# avoccado-avr-pcb-yolandi.net
KiCad netlist of a schematic drawn in EAGLE
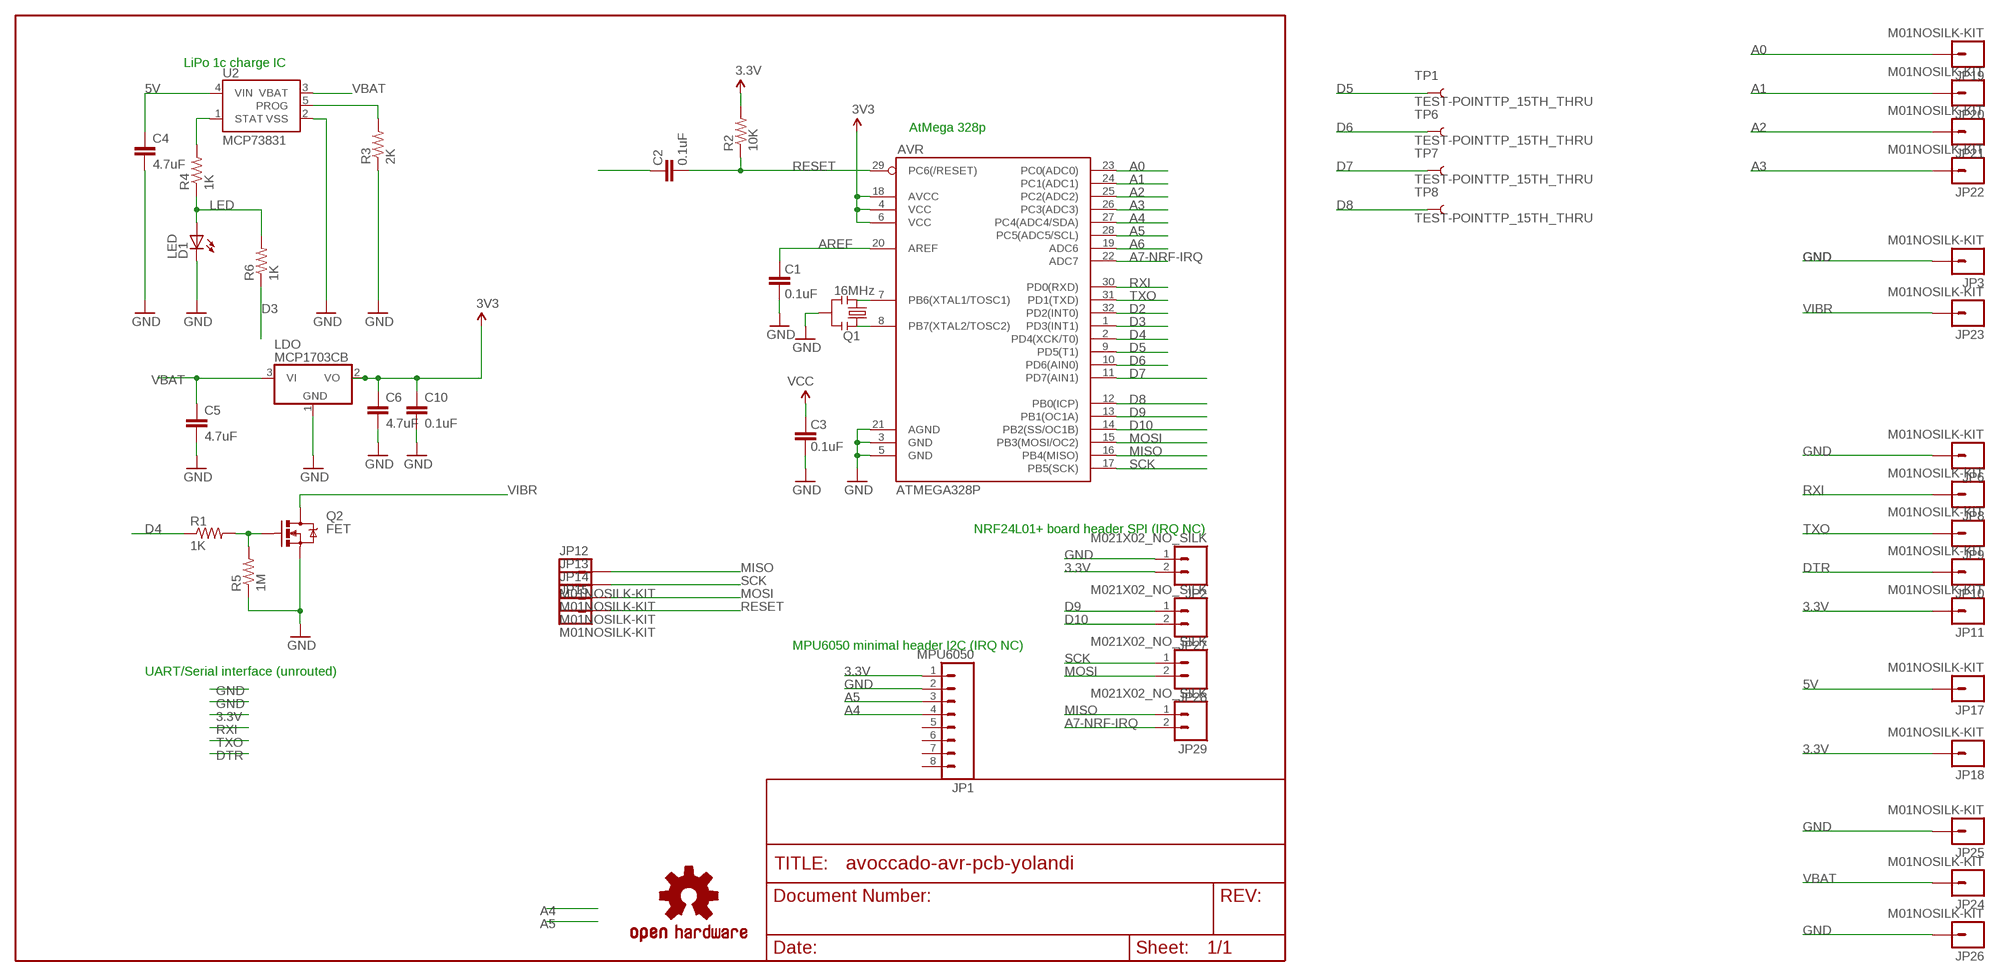
[diagram p0: schematic, sheet 1]

(export (version "E")
  (design (tool "Eeschema 10.0.6"))
  (components
    (comp (ref "AVR")
      (value "ATMEGA328P")
      (footprint "eagle-import:TQFP32-08")
      (libsource (lib "eagle-import") (part "ATMEGA328_SMT"))
    )
    (comp (ref "C1")
      (value "0.1uF")
      (footprint "eagle-import:C0402")
      (libsource (lib "eagle-import") (part "CAP0402"))
    )
    (comp (ref "C2")
      (value "0.1uF")
      (footprint "eagle-import:C0402")
      (libsource (lib "eagle-import") (part "CAP0402"))
    )
    (comp (ref "C3")
      (value "0.1uF")
      (footprint "eagle-import:C0402")
      (libsource (lib "eagle-import") (part "CAP0402"))
    )
    (comp (ref "C4")
      (value "4.7uF")
      (footprint "eagle-import:0603-CAP")
      (libsource (lib "eagle-import") (part "4.7UF-6.3V-10%(0603)0603"))
    )
    (comp (ref "C5")
      (value "4.7uF")
      (footprint "eagle-import:0603-CAP")
      (libsource (lib "eagle-import") (part "4.7UF-6.3V-10%(0603)0603"))
    )
    (comp (ref "C6")
      (value "4.7uF")
      (footprint "eagle-import:0603-CAP")
      (libsource (lib "eagle-import") (part "4.7UF-6.3V-10%(0603)0603"))
    )
    (comp (ref "C10")
      (value "0.1uF")
      (footprint "eagle-import:C0402")
      (libsource (lib "eagle-import") (part "CAP0402"))
    )
    (comp (ref "D1")
      (value "LED")
      (footprint "eagle-import:LED-0603")
      (libsource (lib "eagle-import") (part "LED0603"))
    )
    (comp (ref "JP1")
      (value "MPU6050")
      (footprint "eagle-import:1X08_PIN1_NO_SILK")
      (libsource (lib "eagle-import") (part "M08NO_SILK"))
    )
    (comp (ref "JP2")
      (value "M021X02_NO_SILK")
      (footprint "eagle-import:1X02_NO_SILK")
      (libsource (lib "eagle-import") (part "M021X02_NO_SILK"))
    )
    (comp (ref "JP3")
      (value "M01NOSILK-KIT")
      (footprint "eagle-import:1X01NS-KIT")
      (libsource (lib "eagle-import") (part "M01NOSILK-KIT"))
    )
    (comp (ref "JP6")
      (value "M01NOSILK-KIT")
      (footprint "eagle-import:1X01NS-KIT")
      (libsource (lib "eagle-import") (part "M01NOSILK-KIT"))
    )
    (comp (ref "JP8")
      (value "M01NOSILK-KIT")
      (footprint "eagle-import:1X01NS-KIT")
      (libsource (lib "eagle-import") (part "M01NOSILK-KIT"))
    )
    (comp (ref "JP9")
      (value "M01NOSILK-KIT")
      (footprint "eagle-import:1X01NS-KIT")
      (libsource (lib "eagle-import") (part "M01NOSILK-KIT"))
    )
    (comp (ref "JP10")
      (value "M01NOSILK-KIT")
      (footprint "eagle-import:1X01NS-KIT")
      (libsource (lib "eagle-import") (part "M01NOSILK-KIT"))
    )
    (comp (ref "JP11")
      (value "M01NOSILK-KIT")
      (footprint "eagle-import:1X01NS-KIT")
      (libsource (lib "eagle-import") (part "M01NOSILK-KIT"))
    )
    (comp (ref "JP12")
      (value "M01NOSILK-KIT")
      (footprint "eagle-import:1X01NS-KIT")
      (libsource (lib "eagle-import") (part "M01NOSILK-KIT"))
    )
    (comp (ref "JP13")
      (value "M01NOSILK-KIT")
      (footprint "eagle-import:1X01NS-KIT")
      (libsource (lib "eagle-import") (part "M01NOSILK-KIT"))
    )
    (comp (ref "JP14")
      (value "M01NOSILK-KIT")
      (footprint "eagle-import:1X01NS-KIT")
      (libsource (lib "eagle-import") (part "M01NOSILK-KIT"))
    )
    (comp (ref "JP15")
      (value "M01NOSILK-KIT")
      (footprint "eagle-import:1X01NS-KIT")
      (libsource (lib "eagle-import") (part "M01NOSILK-KIT"))
    )
    (comp (ref "JP17")
      (value "M01NOSILK-KIT")
      (footprint "eagle-import:1X01NS-KIT")
      (libsource (lib "eagle-import") (part "M01NOSILK-KIT"))
    )
    (comp (ref "JP18")
      (value "M01NOSILK-KIT")
      (footprint "eagle-import:1X01NS-KIT")
      (libsource (lib "eagle-import") (part "M01NOSILK-KIT"))
    )
    (comp (ref "JP19")
      (value "M01NOSILK-KIT")
      (footprint "eagle-import:1X01NS-KIT")
      (libsource (lib "eagle-import") (part "M01NOSILK-KIT"))
    )
    (comp (ref "JP20")
      (value "M01NOSILK-KIT")
      (footprint "eagle-import:1X01NS-KIT")
      (libsource (lib "eagle-import") (part "M01NOSILK-KIT"))
    )
    (comp (ref "JP21")
      (value "M01NOSILK-KIT")
      (footprint "eagle-import:1X01NS-KIT")
      (libsource (lib "eagle-import") (part "M01NOSILK-KIT"))
    )
    (comp (ref "JP22")
      (value "M01NOSILK-KIT")
      (footprint "eagle-import:1X01NS-KIT")
      (libsource (lib "eagle-import") (part "M01NOSILK-KIT"))
    )
    (comp (ref "JP23")
      (value "M01NOSILK-KIT")
      (footprint "eagle-import:1X01NS-KIT")
      (libsource (lib "eagle-import") (part "M01NOSILK-KIT"))
    )
    (comp (ref "JP24")
      (value "M01NOSILK-KIT")
      (footprint "eagle-import:1X01NS-KIT")
      (libsource (lib "eagle-import") (part "M01NOSILK-KIT"))
    )
    (comp (ref "JP25")
      (value "M01NOSILK-KIT")
      (footprint "eagle-import:1X01NS-KIT")
      (libsource (lib "eagle-import") (part "M01NOSILK-KIT"))
    )
    (comp (ref "JP26")
      (value "M01NOSILK-KIT")
      (footprint "eagle-import:1X01NS-KIT")
      (libsource (lib "eagle-import") (part "M01NOSILK-KIT"))
    )
    (comp (ref "JP27")
      (value "M021X02_NO_SILK")
      (footprint "eagle-import:1X02_NO_SILK")
      (libsource (lib "eagle-import") (part "M021X02_NO_SILK"))
    )
    (comp (ref "JP28")
      (value "M021X02_NO_SILK")
      (footprint "eagle-import:1X02_NO_SILK")
      (libsource (lib "eagle-import") (part "M021X02_NO_SILK"))
    )
    (comp (ref "JP29")
      (value "M021X02_NO_SILK")
      (footprint "eagle-import:1X02_NO_SILK")
      (libsource (lib "eagle-import") (part "M021X02_NO_SILK"))
    )
    (comp (ref "LDO")
      (value "MCP1703CB")
      (footprint "eagle-import:SOT23")
      (libsource (lib "eagle-import") (part "MCP1703CB"))
    )
    (comp (ref "LOGO1")
      (value "OSHW-LOGOS")
      (footprint "eagle-import:OSHW-LOGO-S")
      (libsource (lib "eagle-import") (part "OSHW-LOGOS"))
    )
    (comp (ref "Q1")
      (value "16MHz")
      (footprint "eagle-import:RESONATOR-SMD")
      (libsource (lib "eagle-import") (part "RESONATORSMD"))
    )
    (comp (ref "Q2")
      (value "FET")
      (footprint "eagle-import:SOT323")
      (libsource (lib "eagle-import") (part "MOSFET-NCHANNEL2N7002PW"))
    )
    (comp (ref "R1")
      (value "1K")
      (footprint "eagle-import:0603-RES")
      (libsource (lib "eagle-import") (part "RESISTOR0603"))
    )
    (comp (ref "R2")
      (value "10K")
      (footprint "eagle-import:0603-RES")
      (libsource (lib "eagle-import") (part "RESISTOR0603"))
    )
    (comp (ref "R3")
      (value "2K")
      (footprint "eagle-import:0603-RES")
      (libsource (lib "eagle-import") (part "RESISTOR0603"))
    )
    (comp (ref "R4")
      (value "1K")
      (footprint "eagle-import:0603-RES")
      (libsource (lib "eagle-import") (part "RESISTOR0603"))
    )
    (comp (ref "R5")
      (value "1M")
      (footprint "eagle-import:0603-RES")
      (libsource (lib "eagle-import") (part "RESISTOR0603"))
    )
    (comp (ref "R6")
      (value "1K")
      (footprint "eagle-import:0603-RES")
      (libsource (lib "eagle-import") (part "RESISTOR0603"))
    )
    (comp (ref "TP1")
      (value "TEST-POINTTP_15TH_THRU")
      (footprint "eagle-import:TP_15TH")
      (libsource (lib "eagle-import") (part "TEST-POINTTP_15TH_THRU"))
    )
    (comp (ref "TP6")
      (value "TEST-POINTTP_15TH_THRU")
      (footprint "eagle-import:TP_15TH")
      (libsource (lib "eagle-import") (part "TEST-POINTTP_15TH_THRU"))
    )
    (comp (ref "TP7")
      (value "TEST-POINTTP_15TH_THRU")
      (footprint "eagle-import:TP_15TH")
      (libsource (lib "eagle-import") (part "TEST-POINTTP_15TH_THRU"))
    )
    (comp (ref "TP8")
      (value "TEST-POINTTP_15TH_THRU")
      (footprint "eagle-import:TP_15TH")
      (libsource (lib "eagle-import") (part "TEST-POINTTP_15TH_THRU"))
    )
    (comp (ref "U2")
      (value "MCP73831")
      (footprint "eagle-import:SOT23-5")
      (libsource (lib "eagle-import") (part "MCP73831"))
    )
  )
  (nets
    (net (code "1") (name "/5V") (class "Default")
      (node (ref "C4") (pin "1") (pinfunction "1_1") (pintype "passive"))
      (node (ref "JP17") (pin "1") (pinfunction "1_1") (pintype "passive"))
      (node (ref "U2") (pin "4") (pinfunction "VIN_4") (pintype "power_in"))
    )
    (net (code "2") (name "/A0") (class "Default")
      (node (ref "AVR") (pin "23") (pinfunction "PC0(ADC0)_23") (pintype "bidirectional"))
      (node (ref "JP19") (pin "1") (pinfunction "1_1") (pintype "passive"))
    )
    (net (code "3") (name "/A1") (class "Default")
      (node (ref "AVR") (pin "24") (pinfunction "PC1(ADC1)_24") (pintype "bidirectional"))
      (node (ref "JP20") (pin "1") (pinfunction "1_1") (pintype "passive"))
    )
    (net (code "4") (name "/A2") (class "Default")
      (node (ref "AVR") (pin "25") (pinfunction "PC2(ADC2)_25") (pintype "bidirectional"))
      (node (ref "JP21") (pin "1") (pinfunction "1_1") (pintype "passive"))
    )
    (net (code "5") (name "/A3") (class "Default")
      (node (ref "AVR") (pin "26") (pinfunction "PC3(ADC3)_26") (pintype "bidirectional"))
      (node (ref "JP22") (pin "1") (pinfunction "1_1") (pintype "passive"))
    )
    (net (code "6") (name "/A4") (class "Default")
      (node (ref "AVR") (pin "27") (pinfunction "PC4(ADC4/SDA)_27") (pintype "bidirectional"))
      (node (ref "JP1") (pin "4") (pinfunction "4_4") (pintype "passive"))
    )
    (net (code "7") (name "/A5") (class "Default")
      (node (ref "AVR") (pin "28") (pinfunction "PC5(ADC5/SCL)_28") (pintype "bidirectional"))
      (node (ref "JP1") (pin "3") (pinfunction "3_3") (pintype "passive"))
    )
    (net (code "8") (name "/A6") (class "Default")
      (node (ref "AVR") (pin "19") (pinfunction "ADC6_19") (pintype "bidirectional"))
    )
    (net (code "9") (name "/A7-NRF-IRQ") (class "Default")
      (node (ref "AVR") (pin "22") (pinfunction "ADC7_22") (pintype "bidirectional"))
      (node (ref "JP29") (pin "2") (pinfunction "2_2") (pintype "passive"))
    )
    (net (code "10") (name "/AREF") (class "Default")
      (node (ref "AVR") (pin "20") (pinfunction "AREF_20") (pintype "bidirectional"))
      (node (ref "C1") (pin "2") (pinfunction "2_2") (pintype "passive"))
    )
    (net (code "11") (name "/D2") (class "Default")
      (node (ref "AVR") (pin "32") (pinfunction "PD2(INT0)_32") (pintype "bidirectional"))
    )
    (net (code "12") (name "/D3") (class "Default")
      (node (ref "AVR") (pin "1") (pinfunction "PD3(INT1)_1") (pintype "bidirectional"))
      (node (ref "R6") (pin "1") (pinfunction "1_1") (pintype "passive"))
    )
    (net (code "13") (name "/D4") (class "Default")
      (node (ref "AVR") (pin "2") (pinfunction "PD4(XCK/T0)_2") (pintype "bidirectional"))
      (node (ref "R1") (pin "1") (pinfunction "1_1") (pintype "passive"))
    )
    (net (code "14") (name "/D5") (class "Default")
      (node (ref "AVR") (pin "9") (pinfunction "PD5(T1)_9") (pintype "bidirectional"))
      (node (ref "TP1") (pin "P$1") (pinfunction "1_P$1") (pintype "bidirectional"))
    )
    (net (code "15") (name "/D6") (class "Default")
      (node (ref "AVR") (pin "10") (pinfunction "PD6(AIN0)_10") (pintype "bidirectional"))
      (node (ref "TP6") (pin "P$1") (pinfunction "1_P$1") (pintype "bidirectional"))
    )
    (net (code "16") (name "/D7") (class "Default")
      (node (ref "AVR") (pin "11") (pinfunction "PD7(AIN1)_11") (pintype "bidirectional"))
      (node (ref "TP7") (pin "P$1") (pinfunction "1_P$1") (pintype "bidirectional"))
    )
    (net (code "17") (name "/D8") (class "Default")
      (node (ref "AVR") (pin "12") (pinfunction "PB0(ICP)_12") (pintype "bidirectional"))
      (node (ref "TP8") (pin "P$1") (pinfunction "1_P$1") (pintype "bidirectional"))
    )
    (net (code "18") (name "/D9") (class "Default")
      (node (ref "AVR") (pin "13") (pinfunction "PB1(OC1A)_13") (pintype "bidirectional"))
      (node (ref "JP27") (pin "1") (pinfunction "1_1") (pintype "passive"))
    )
    (net (code "19") (name "/D10") (class "Default")
      (node (ref "AVR") (pin "14") (pinfunction "PB2(SS/OC1B)_14") (pintype "bidirectional"))
      (node (ref "JP27") (pin "2") (pinfunction "2_2") (pintype "passive"))
    )
    (net (code "20") (name "/DTR") (class "Default")
      (node (ref "C2") (pin "2") (pinfunction "2_2") (pintype "passive"))
      (node (ref "JP10") (pin "1") (pinfunction "1_1") (pintype "passive"))
    )
    (net (code "21") (name "/LED") (class "Default")
      (node (ref "D1") (pin "A") (pinfunction "A_A") (pintype "passive"))
      (node (ref "R4") (pin "1") (pinfunction "1_1") (pintype "passive"))
      (node (ref "R6") (pin "2") (pinfunction "2_2") (pintype "passive"))
    )
    (net (code "22") (name "/MISO") (class "Default")
      (node (ref "AVR") (pin "16") (pinfunction "PB4(MISO)_16") (pintype "bidirectional"))
      (node (ref "JP12") (pin "1") (pinfunction "1_1") (pintype "passive"))
      (node (ref "JP29") (pin "1") (pinfunction "1_1") (pintype "passive"))
    )
    (net (code "23") (name "/MOSI") (class "Default")
      (node (ref "AVR") (pin "15") (pinfunction "PB3(MOSI/OC2)_15") (pintype "bidirectional"))
      (node (ref "JP14") (pin "1") (pinfunction "1_1") (pintype "passive"))
      (node (ref "JP28") (pin "2") (pinfunction "2_2") (pintype "passive"))
    )
    (net (code "24") (name "/RESET") (class "Default")
      (node (ref "AVR") (pin "29") (pinfunction "PC6(/RESET)_29") (pintype "bidirectional"))
      (node (ref "C2") (pin "1") (pinfunction "1_1") (pintype "passive"))
      (node (ref "JP15") (pin "1") (pinfunction "1_1") (pintype "passive"))
      (node (ref "R2") (pin "1") (pinfunction "1_1") (pintype "passive"))
    )
    (net (code "25") (name "/RXI") (class "Default")
      (node (ref "AVR") (pin "30") (pinfunction "PD0(RXD)_30") (pintype "bidirectional"))
      (node (ref "JP8") (pin "1") (pinfunction "1_1") (pintype "passive"))
    )
    (net (code "26") (name "/SCK") (class "Default")
      (node (ref "AVR") (pin "17") (pinfunction "PB5(SCK)_17") (pintype "bidirectional"))
      (node (ref "JP13") (pin "1") (pinfunction "1_1") (pintype "passive"))
      (node (ref "JP28") (pin "1") (pinfunction "1_1") (pintype "passive"))
    )
    (net (code "27") (name "/TXO") (class "Default")
      (node (ref "AVR") (pin "31") (pinfunction "PD1(TXD)_31") (pintype "bidirectional"))
      (node (ref "JP9") (pin "1") (pinfunction "1_1") (pintype "passive"))
    )
    (net (code "28") (name "/VBAT") (class "Default")
      (node (ref "C5") (pin "1") (pinfunction "1_1") (pintype "passive"))
      (node (ref "JP24") (pin "1") (pinfunction "1_1") (pintype "passive"))
      (node (ref "LDO") (pin "3") (pinfunction "VI_3") (pintype "input"))
      (node (ref "U2") (pin "3") (pinfunction "VBAT_3") (pintype "power_in"))
    )
    (net (code "29") (name "/VIBR") (class "Default")
      (node (ref "JP23") (pin "1") (pinfunction "1_1") (pintype "passive"))
      (node (ref "Q2") (pin "3") (pinfunction "D_3") (pintype "passive"))
    )
    (net (code "30") (name "3.3V") (class "Default")
      (node (ref "AVR") (pin "18") (pinfunction "AVCC_18") (pintype "bidirectional"))
      (node (ref "AVR") (pin "4") (pinfunction "VCC_4") (pintype "bidirectional"))
      (node (ref "AVR") (pin "6") (pinfunction "VCC_6") (pintype "bidirectional"))
      (node (ref "C10") (pin "1") (pinfunction "1_1") (pintype "passive"))
      (node (ref "C3") (pin "2") (pinfunction "2_2") (pintype "passive"))
      (node (ref "C6") (pin "1") (pinfunction "1_1") (pintype "passive"))
      (node (ref "JP1") (pin "1") (pinfunction "1_1") (pintype "passive"))
      (node (ref "JP11") (pin "1") (pinfunction "1_1") (pintype "passive"))
      (node (ref "JP18") (pin "1") (pinfunction "1_1") (pintype "passive"))
      (node (ref "JP2") (pin "2") (pinfunction "2_2") (pintype "passive"))
      (node (ref "LDO") (pin "2") (pinfunction "VO_2") (pintype "passive"))
      (node (ref "R2") (pin "2") (pinfunction "2_2") (pintype "passive"))
    )
    (net (code "31") (name "GND") (class "Default")
      (node (ref "AVR") (pin "21") (pinfunction "AGND_21") (pintype "bidirectional"))
      (node (ref "AVR") (pin "3") (pinfunction "GND_3") (pintype "bidirectional"))
      (node (ref "AVR") (pin "5") (pinfunction "GND_5") (pintype "bidirectional"))
      (node (ref "C1") (pin "1") (pinfunction "1_1") (pintype "passive"))
      (node (ref "C10") (pin "2") (pinfunction "2_2") (pintype "passive"))
      (node (ref "C3") (pin "1") (pinfunction "1_1") (pintype "passive"))
      (node (ref "C4") (pin "2") (pinfunction "2_2") (pintype "passive"))
      (node (ref "C5") (pin "2") (pinfunction "2_2") (pintype "passive"))
      (node (ref "C6") (pin "2") (pinfunction "2_2") (pintype "passive"))
      (node (ref "D1") (pin "C") (pinfunction "C_C") (pintype "passive"))
      (node (ref "JP1") (pin "2") (pinfunction "2_2") (pintype "passive"))
      (node (ref "JP2") (pin "1") (pinfunction "1_1") (pintype "passive"))
      (node (ref "JP25") (pin "1") (pinfunction "1_1") (pintype "passive"))
      (node (ref "JP26") (pin "1") (pinfunction "1_1") (pintype "passive"))
      (node (ref "JP3") (pin "1") (pinfunction "1_1") (pintype "passive"))
      (node (ref "JP6") (pin "1") (pinfunction "1_1") (pintype "passive"))
      (node (ref "LDO") (pin "1") (pinfunction "GND_1") (pintype "passive"))
      (node (ref "Q1") (pin "2") (pinfunction "2_2") (pintype "passive"))
      (node (ref "Q2") (pin "2") (pinfunction "S_2") (pintype "passive"))
      (node (ref "R3") (pin "1") (pinfunction "1_1") (pintype "passive"))
      (node (ref "R5") (pin "1") (pinfunction "1_1") (pintype "passive"))
      (node (ref "U2") (pin "2") (pinfunction "VSS_2") (pintype "power_in"))
    )
    (net (code "32") (name "Net-(AVR-PB6(XTAL1{slash}TOSC1))") (class "Default")
      (node (ref "AVR") (pin "7") (pinfunction "PB6(XTAL1/TOSC1)_7") (pintype "bidirectional"))
      (node (ref "Q1") (pin "3") (pinfunction "3_3") (pintype "passive"))
    )
    (net (code "33") (name "Net-(AVR-PB7(XTAL2{slash}TOSC2))") (class "Default")
      (node (ref "AVR") (pin "8") (pinfunction "PB7(XTAL2/TOSC2)_8") (pintype "bidirectional"))
      (node (ref "Q1") (pin "1") (pinfunction "1_1") (pintype "passive"))
    )
    (net (code "34") (name "Net-(Q2-G)") (class "Default")
      (node (ref "Q2") (pin "1") (pinfunction "G_1") (pintype "passive"))
      (node (ref "R1") (pin "2") (pinfunction "2_2") (pintype "passive"))
      (node (ref "R5") (pin "2") (pinfunction "2_2") (pintype "passive"))
    )
    (net (code "35") (name "Net-(U2-PROG)") (class "Default")
      (node (ref "R3") (pin "2") (pinfunction "2_2") (pintype "passive"))
      (node (ref "U2") (pin "5") (pinfunction "PROG_5") (pintype "input"))
    )
    (net (code "36") (name "Net-(U2-STAT)") (class "Default")
      (node (ref "R4") (pin "2") (pinfunction "2_2") (pintype "passive"))
      (node (ref "U2") (pin "1") (pinfunction "STAT_1") (pintype "output"))
    )
    (net (code "37") (name "unconnected-(JP1-Pad5)") (class "Default")
      (node (ref "JP1") (pin "5") (pinfunction "5_5") (pintype "passive"))
    )
    (net (code "38") (name "unconnected-(JP1-Pad6)") (class "Default")
      (node (ref "JP1") (pin "6") (pinfunction "6_6") (pintype "passive"))
    )
    (net (code "39") (name "unconnected-(JP1-Pad7)") (class "Default")
      (node (ref "JP1") (pin "7") (pinfunction "7_7") (pintype "passive"))
    )
    (net (code "40") (name "unconnected-(JP1-Pad8)") (class "Default")
      (node (ref "JP1") (pin "8") (pinfunction "8_8") (pintype "passive"))
    )
  )
)
